# pca10040_sheet3_buttons_and_leds.net
KiCad netlist of a schematic drawn in Altium Designer
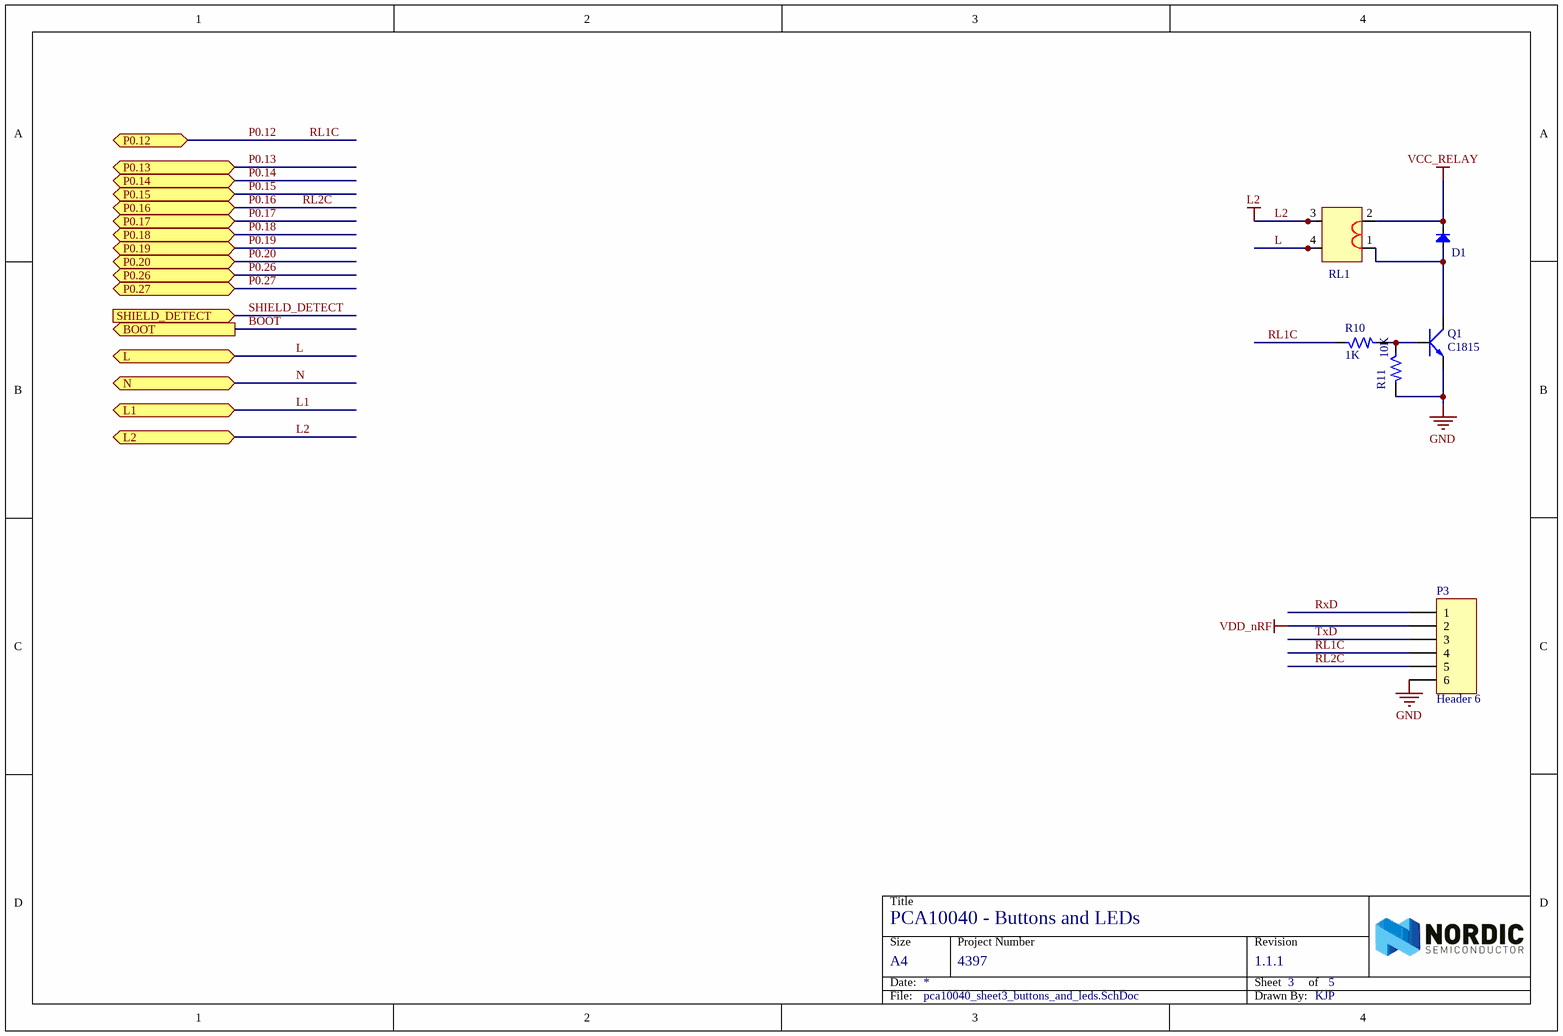
[diagram p0: pca10040_sheet3_buttons_and_leds.SchDoc]

(export (version "E")
  (design (tool "Eeschema 10.0.6"))
  (components
    (comp (ref "D1")
      (value "Diode SMD")
      (footprint "DIO-SMD-123")
      (description "Default Diode")
      (fields (field (name "PUBLISHER") "Altium Limited"))
      (libsource (lib "LIBRARY") (part "Diode SMD"))
    )
    (comp (ref "P3")
      (value "Header 6")
      (footprint "HDR1X6")
      (description "Header, 6-Pin")
      (fields (field (name "PUBLISHER") "Altium Limited"))
      (libsource (lib "Miscellaneous Connectors") (part "Header 6"))
    )
    (comp (ref "Q1")
      (value "C1815")
      (footprint "SOT23B")
      (description "NPN 600mW, ECB")
      (libsource (lib "hatcatbietbay") (part "C1815"))
    )
    (comp (ref "R10")
      (value "1K")
      (footprint "PcbLib1:0603")
      (description "Resistor 1/4W")
      (libsource (lib "hatcatbietbay") (part "R"))
    )
    (comp (ref "R11")
      (value "10K")
      (footprint "PcbLib1:0603")
      (description "Resistor 1/4W")
      (libsource (lib "hatcatbietbay") (part "R"))
    )
    (comp (ref "RL1")
      (value "Component_1")
      (footprint "AZ7705")
      (libsource (lib "Zettler") (part "Component_1"))
    )
  )
  (nets
    (net (code "2") (name "/L") (class "Default") (node (ref "RL1") (pin "4") (pintype "passive")))
    (net (code "5") (name "/P0.12") (class "Default")
      (node (ref "P3") (pin "4") (pinfunction "4_4") (pintype "passive"))
      (node (ref "R10") (pin "1") (pinfunction "1_1") (pintype "passive"))
    )
    (net (code "9") (name "/P0.16") (class "Default")
      (node (ref "P3") (pin "5") (pinfunction "5_5") (pintype "passive"))
    )
    (net (code "16") (name "/RxD") (class "Default")
      (node (ref "P3") (pin "1") (pinfunction "1_1") (pintype "passive"))
    )
    (net (code "18") (name "/TxD") (class "Default")
      (node (ref "P3") (pin "3") (pinfunction "3_3") (pintype "passive"))
    )
    (net (code "19") (name "GND") (class "Default")
      (node (ref "P3") (pin "6") (pinfunction "6_6") (pintype "passive"))
      (node (ref "Q1") (pin "3") (pinfunction "E_3") (pintype "passive"))
      (node (ref "R11") (pin "2") (pinfunction "2_2") (pintype "passive"))
    )
    (net (code "20") (name "L2") (class "Default") (node (ref "RL1") (pin "3") (pintype "passive")))
    (net (code "21") (name "Net-(D1-A)") (class "Default")
      (node (ref "D1") (pin "1") (pinfunction "A_1") (pintype "passive"))
      (node (ref "Q1") (pin "2") (pinfunction "C_2") (pintype "passive"))
      (node (ref "RL1") (pin "1") (pintype "passive"))
    )
    (net (code "22") (name "Net-(Q1-B)") (class "Default")
      (node (ref "Q1") (pin "1") (pinfunction "B_1") (pintype "passive"))
      (node (ref "R10") (pin "2") (pinfunction "2_2") (pintype "passive"))
      (node (ref "R11") (pin "1") (pinfunction "1_1") (pintype "passive"))
    )
    (net (code "23") (name "VCC_RELAY") (class "Default")
      (node (ref "D1") (pin "2") (pinfunction "K_2") (pintype "passive"))
      (node (ref "RL1") (pin "2") (pintype "passive"))
    )
    (net (code "24") (name "VDD_nRF") (class "Default")
      (node (ref "P3") (pin "2") (pinfunction "2_2") (pintype "passive"))
    )
  )
)
